# PIC_MAIN.net
KiCad netlist of a schematic drawn in Altium Designer
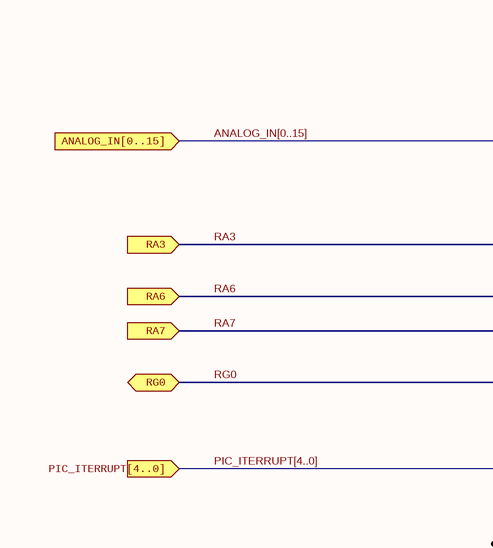
[diagram p0: PIC_MAIN.SchDoc, top left]
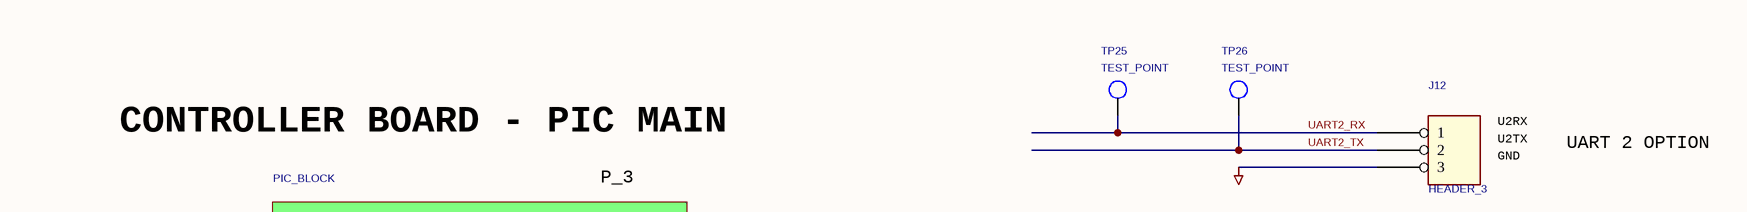
[diagram p1: PIC_MAIN.SchDoc, top right]
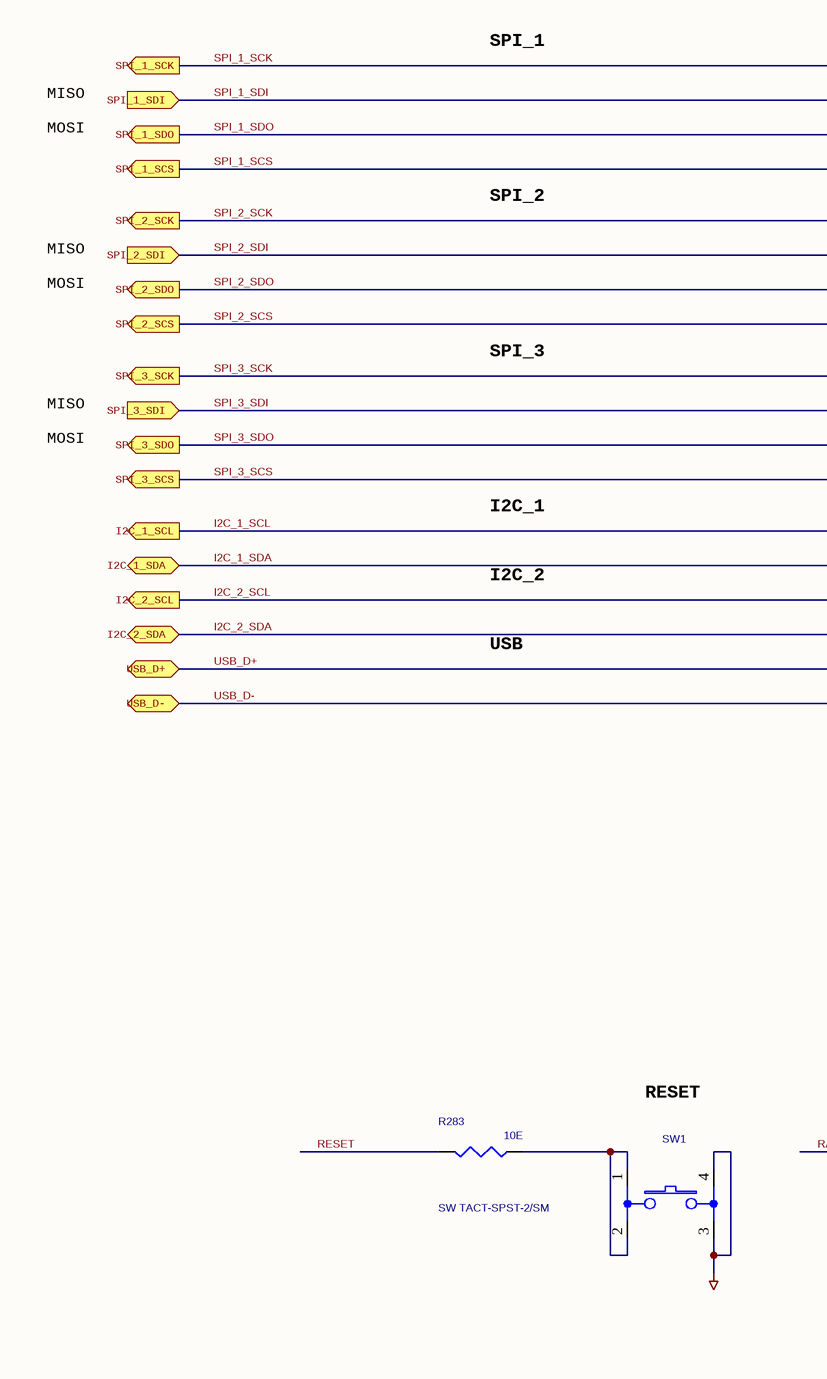
[diagram p2: PIC_MAIN.SchDoc, bottom left]
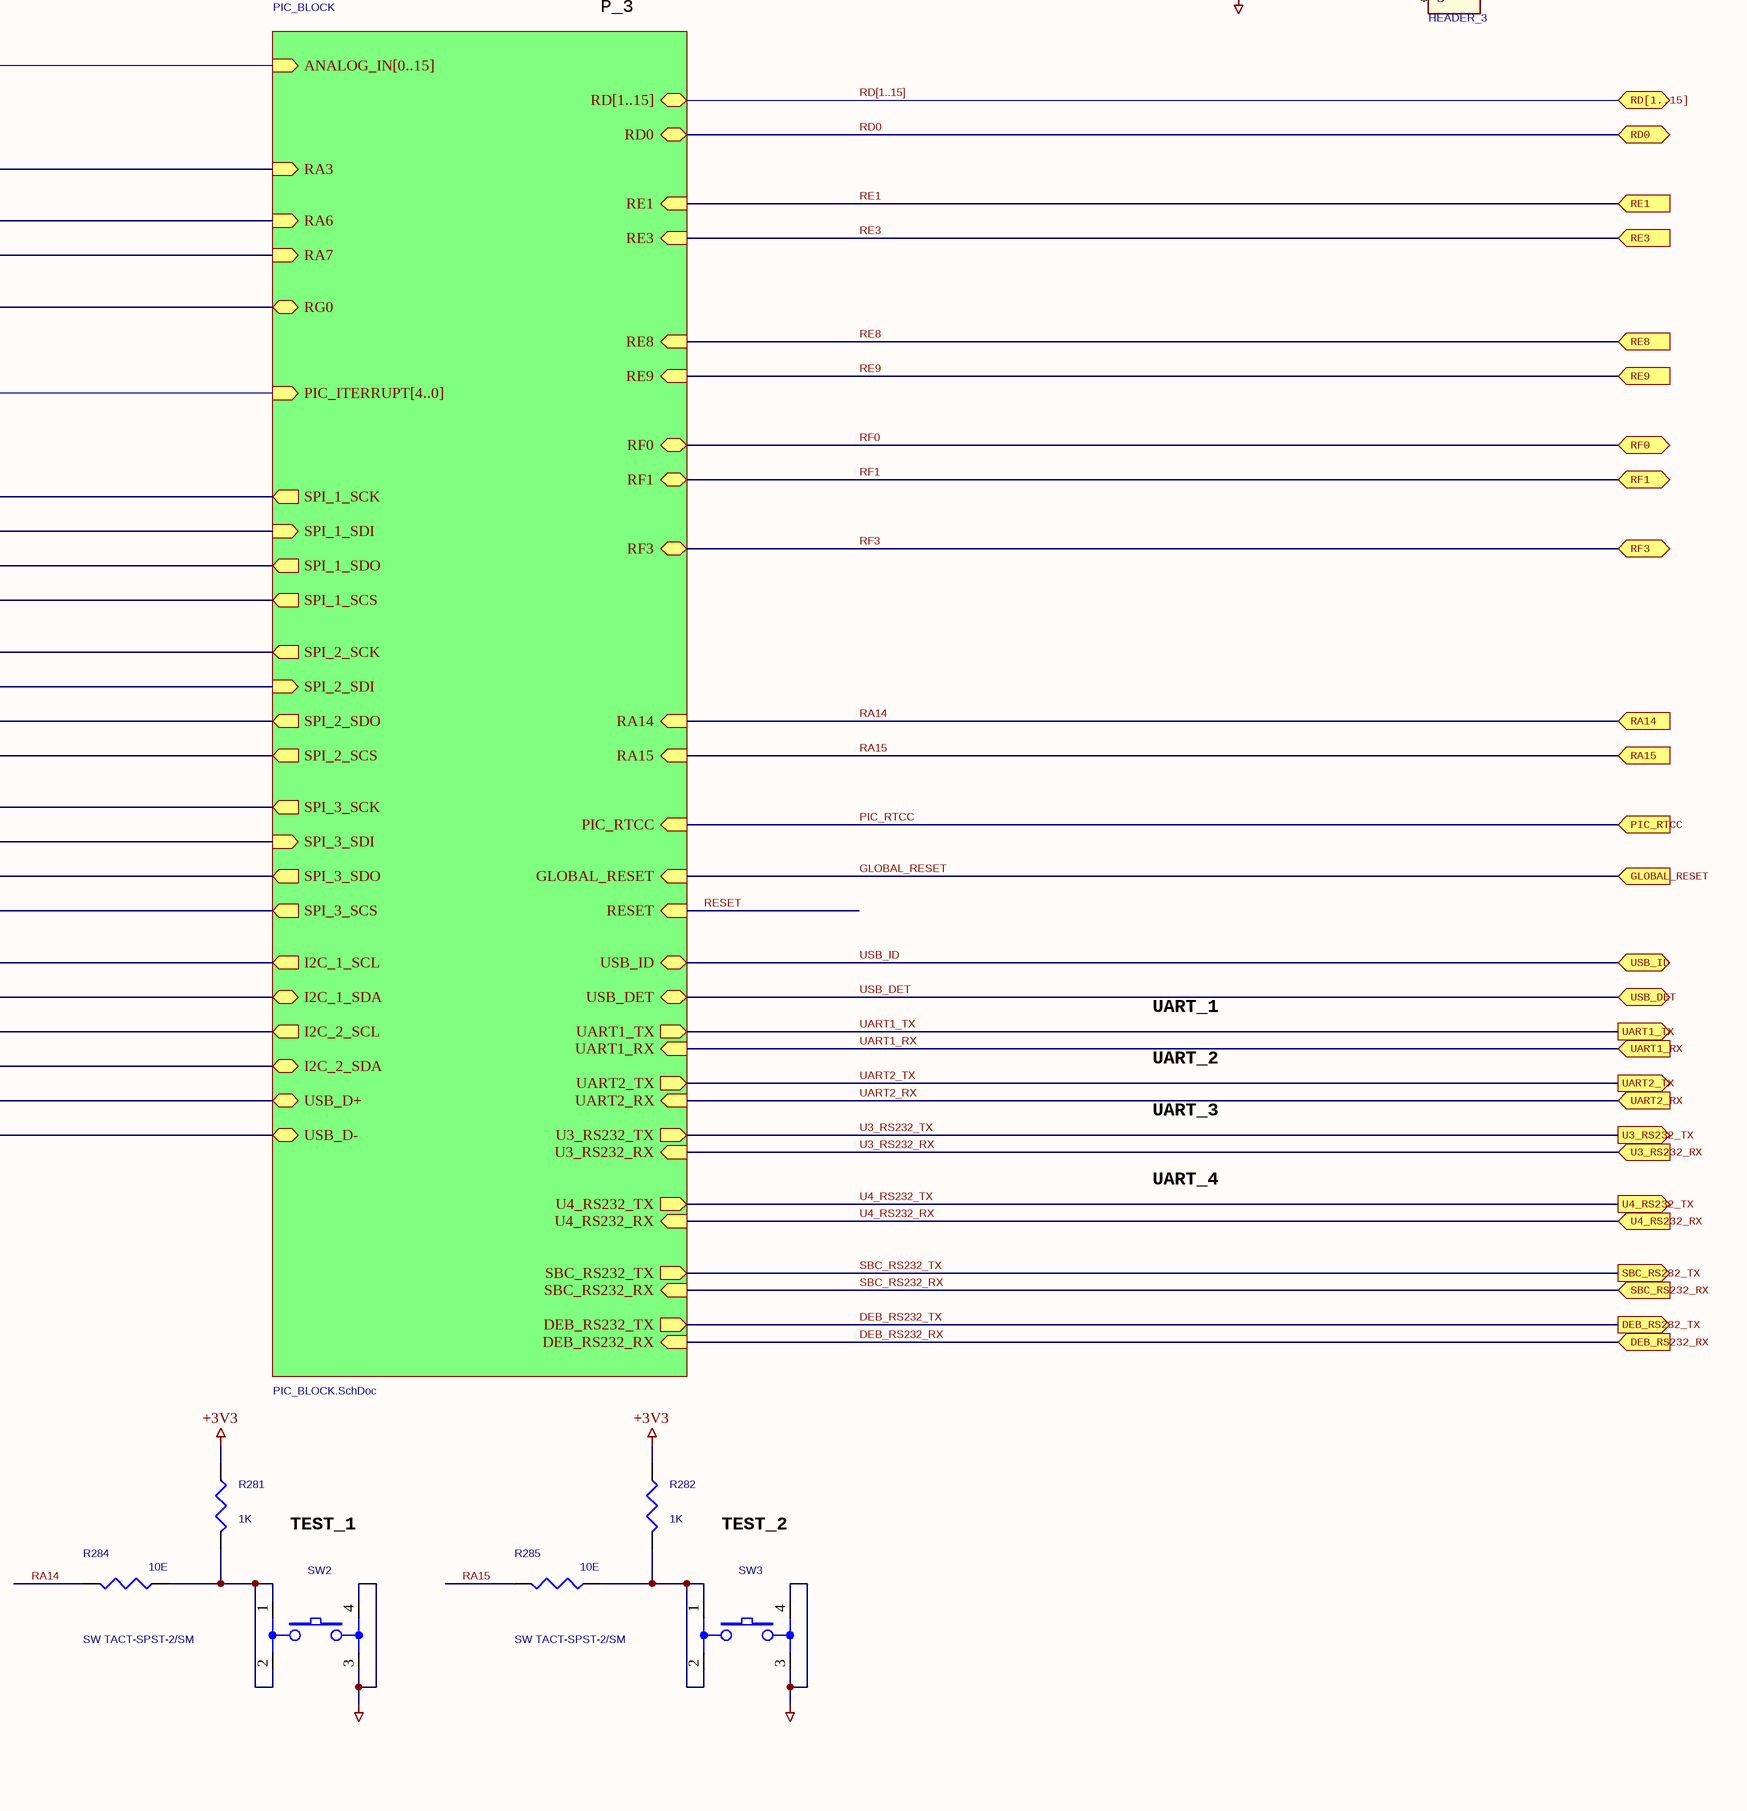
[diagram p3: PIC_MAIN.SchDoc, bottom right]

(export (version "E")
  (design (tool "Eeschema 10.0.6"))
  (components
    (comp (ref "J12") (value "HEADER_3") (footprint "TH_3pin_100mil") (libsource (lib "*") (part "HEADER 3")))
    (comp (ref "R281")
      (value "1K")
      (footprint "0603")
      (fields (field (name "MFG") "YAGEO"))
      (libsource (lib "*") (part "R_Dup1"))
    )
    (comp (ref "R282")
      (value "1K")
      (footprint "0603")
      (fields (field (name "MFG") "YAGEO"))
      (libsource (lib "*") (part "R_Dup1"))
    )
    (comp (ref "R283")
      (value "10E")
      (footprint "0603")
      (fields (field (name "MFG") "YAGEO"))
      (libsource (lib "*") (part "R_Dup1"))
    )
    (comp (ref "R284")
      (value "10E")
      (footprint "0603")
      (fields (field (name "MFG") "YAGEO"))
      (libsource (lib "*") (part "R_Dup1"))
    )
    (comp (ref "R285")
      (value "10E")
      (footprint "0603")
      (fields (field (name "MFG") "YAGEO"))
      (libsource (lib "*") (part "R_Dup1"))
    )
    (comp (ref "SW1")
      (value "SW TACT-SPST-2/SM")
      (footprint "SMT_4PIN")
      (libsource (lib "*") (part "SW TACT-SPST-2/SM"))
    )
    (comp (ref "SW2")
      (value "SW TACT-SPST-2/SM")
      (footprint "SMT_4PIN")
      (libsource (lib "*") (part "SW TACT-SPST-2/SM"))
    )
    (comp (ref "SW3")
      (value "SW TACT-SPST-2/SM")
      (footprint "SMT_4PIN")
      (libsource (lib "*") (part "SW TACT-SPST-2/SM"))
    )
    (comp (ref "TP25")
      (value "TEST_POINT")
      (footprint "TH_1mm")
      (libsource (lib "*") (part "T POINT R_Dup1"))
    )
    (comp (ref "TP26")
      (value "TEST_POINT")
      (footprint "TH_1mm")
      (libsource (lib "*") (part "T POINT R_Dup1"))
    )
  )
  (nets
    (net (code "37") (name "+3V3") (class "Default")
      (node (ref "R281") (pin "1") (pinfunction "1_1") (pintype "passive"))
      (node (ref "R282") (pin "1") (pinfunction "1_1") (pintype "passive"))
    )
    (net (code "51") (name "/RA14") (class "Default")
      (node (ref "R284") (pin "2") (pinfunction "2_2") (pintype "passive"))
    )
    (net (code "52") (name "/RA15") (class "Default")
      (node (ref "R285") (pin "2") (pinfunction "2_2") (pintype "passive"))
    )
    (net (code "59") (name "/RESET") (class "Default")
      (node (ref "R283") (pin "2") (pinfunction "2_2") (pintype "passive"))
    )
    (net (code "84") (name "/UART2_RX") (class "Default")
      (node (ref "J12") (pin "1") (pinfunction "1_1") (pintype "passive"))
      (node (ref "TP25") (pin "1") (pinfunction "TP_1") (pintype "passive"))
    )
    (net (code "85") (name "/UART2_TX") (class "Default")
      (node (ref "J12") (pin "2") (pinfunction "2_2") (pintype "passive"))
      (node (ref "TP26") (pin "1") (pinfunction "TP_1") (pintype "passive"))
    )
    (net (code "90") (name "GND_CPU") (class "Default")
      (node (ref "J12") (pin "3") (pinfunction "3_3") (pintype "passive"))
      (node (ref "SW1") (pin "3") (pinfunction "3_3") (pintype "passive"))
      (node (ref "SW1") (pin "4") (pinfunction "4_4") (pintype "passive"))
      (node (ref "SW2") (pin "3") (pinfunction "3_3") (pintype "passive"))
      (node (ref "SW2") (pin "4") (pinfunction "4_4") (pintype "passive"))
      (node (ref "SW3") (pin "3") (pinfunction "3_3") (pintype "passive"))
      (node (ref "SW3") (pin "4") (pinfunction "4_4") (pintype "passive"))
    )
    (net (code "91") (name "Net-(R281-Pad2)") (class "Default")
      (node (ref "R281") (pin "2") (pinfunction "2_2") (pintype "passive"))
      (node (ref "R284") (pin "1") (pinfunction "1_1") (pintype "passive"))
      (node (ref "SW2") (pin "1") (pinfunction "1_1") (pintype "passive"))
      (node (ref "SW2") (pin "2") (pinfunction "2_2") (pintype "passive"))
    )
    (net (code "92") (name "Net-(R282-Pad2)") (class "Default")
      (node (ref "R282") (pin "2") (pinfunction "2_2") (pintype "passive"))
      (node (ref "R285") (pin "1") (pinfunction "1_1") (pintype "passive"))
      (node (ref "SW3") (pin "1") (pinfunction "1_1") (pintype "passive"))
      (node (ref "SW3") (pin "2") (pinfunction "2_2") (pintype "passive"))
    )
    (net (code "93") (name "Net-(R283-Pad1)") (class "Default")
      (node (ref "R283") (pin "1") (pinfunction "1_1") (pintype "passive"))
      (node (ref "SW1") (pin "1") (pinfunction "1_1") (pintype "passive"))
      (node (ref "SW1") (pin "2") (pinfunction "2_2") (pintype "passive"))
    )
  )
)
